# Main.net
KiCad netlist of a schematic drawn in Altium Designer
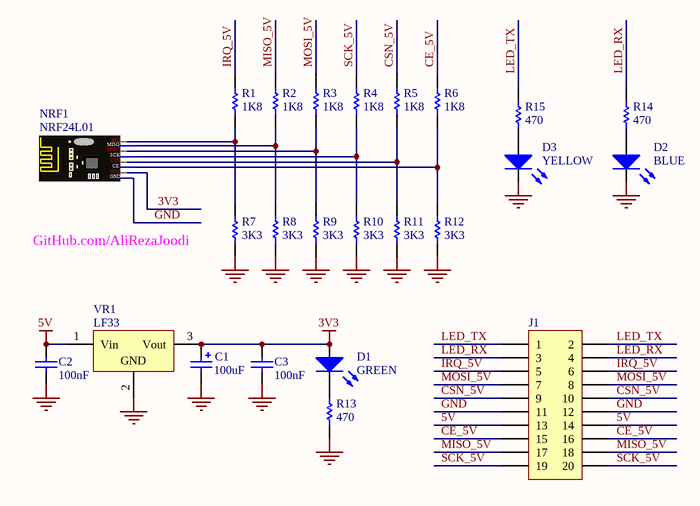
[diagram p0: Main.SchDoc]

(export (version "E")
  (design (tool "Eeschema 10.0.6"))
  (components
    (comp (ref "C1")
      (value "100uF")
      (footprint "CAPPR2.5-6.3x5")
      (description "Polarized Capacitor (Radial)")
      (fields (field (name "MANUFACTURER") "Generic Components") (field (name "PUBLISHER") "Altium Limited"))
      (libsource (lib "Miscellaneous Devices") (part "Cap Pol1"))
    )
    (comp (ref "C2")
      (value "100nF")
      (footprint "CAPNTO2.54-3.05x1.78A")
      (description "Capacitor")
      (fields (field (name "MANUFACTURER") "Generic Components") (field (name "PUBLISHER") "Altium Limited"))
      (libsource (lib "Miscellaneous Devices") (part "Cap"))
    )
    (comp (ref "C3")
      (value "100nF")
      (footprint "CAPNTO2.54-3.05x1.78A")
      (description "Capacitor")
      (fields (field (name "MANUFACTURER") "Generic Components") (field (name "PUBLISHER") "Altium Limited"))
      (libsource (lib "Miscellaneous Devices") (part "Cap"))
    )
    (comp (ref "D1")
      (value "GREEN")
      (footprint "LED-5mm_Red")
      (description "Typical INFRARED GaAs LED")
      (fields (field (name "MANUFACTURER") "Generic Components") (field (name "PUBLISHER") "Altium Limited"))
      (libsource (lib "Miscellaneous Devices") (part "LED"))
    )
    (comp (ref "D2")
      (value "BLUE")
      (footprint "LED-5mm_Red")
      (description "Typical INFRARED GaAs LED")
      (fields (field (name "MANUFACTURER") "Generic Components") (field (name "PUBLISHER") "Altium Limited"))
      (libsource (lib "Miscellaneous Devices") (part "LED"))
    )
    (comp (ref "D3")
      (value "YELLOW")
      (footprint "LED-5mm_Red")
      (description "Typical INFRARED GaAs LED")
      (fields (field (name "MANUFACTURER") "Generic Components") (field (name "PUBLISHER") "Altium Limited"))
      (libsource (lib "Miscellaneous Devices") (part "LED"))
    )
    (comp (ref "J1")
      (value "Header 10X2")
      (footprint "FKV20SN")
      (description "Header, 10-Pin, Dual row")
      (fields (field (name "MANUFACTURER") "Generic Components") (field (name "PUBLISHER") "Altium Limited"))
      (libsource (lib "Miscellaneous Connectors") (part "Header 10X2"))
    )
    (comp (ref "NRF1")
      (value "NRF24L01")
      (footprint "NRF24L01+PA+LNA")
      (libsource (lib "NRF24L01") (part "NRF24L01"))
    )
    (comp (ref "R1")
      (value "1K8")
      (footprint "AXIAL-0.4")
      (description "Resistor")
      (fields (field (name "PUBLISHER") "Altium Limited"))
      (libsource (lib "Miscellaneous Devices") (part "Res1"))
    )
    (comp (ref "R2")
      (value "1K8")
      (footprint "AXIAL-0.4")
      (description "Resistor")
      (fields (field (name "PUBLISHER") "Altium Limited"))
      (libsource (lib "Miscellaneous Devices") (part "Res1"))
    )
    (comp (ref "R3")
      (value "1K8")
      (footprint "AXIAL-0.4")
      (description "Resistor")
      (fields (field (name "PUBLISHER") "Altium Limited"))
      (libsource (lib "Miscellaneous Devices") (part "Res1"))
    )
    (comp (ref "R4")
      (value "1K8")
      (footprint "AXIAL-0.4")
      (description "Resistor")
      (fields (field (name "PUBLISHER") "Altium Limited"))
      (libsource (lib "Miscellaneous Devices") (part "Res1"))
    )
    (comp (ref "R5")
      (value "1K8")
      (footprint "AXIAL-0.4")
      (description "Resistor")
      (fields (field (name "PUBLISHER") "Altium Limited"))
      (libsource (lib "Miscellaneous Devices") (part "Res1"))
    )
    (comp (ref "R6")
      (value "1K8")
      (footprint "AXIAL-0.4")
      (description "Resistor")
      (fields (field (name "PUBLISHER") "Altium Limited"))
      (libsource (lib "Miscellaneous Devices") (part "Res1"))
    )
    (comp (ref "R7")
      (value "3K3")
      (footprint "AXIAL-0.4")
      (description "Resistor")
      (fields (field (name "PUBLISHER") "Altium Limited"))
      (libsource (lib "Miscellaneous Devices") (part "Res1"))
    )
    (comp (ref "R8")
      (value "3K3")
      (footprint "AXIAL-0.4")
      (description "Resistor")
      (fields (field (name "PUBLISHER") "Altium Limited"))
      (libsource (lib "Miscellaneous Devices") (part "Res1"))
    )
    (comp (ref "R9")
      (value "3K3")
      (footprint "AXIAL-0.4")
      (description "Resistor")
      (fields (field (name "PUBLISHER") "Altium Limited"))
      (libsource (lib "Miscellaneous Devices") (part "Res1"))
    )
    (comp (ref "R10")
      (value "3K3")
      (footprint "AXIAL-0.4")
      (description "Resistor")
      (fields (field (name "PUBLISHER") "Altium Limited"))
      (libsource (lib "Miscellaneous Devices") (part "Res1"))
    )
    (comp (ref "R11")
      (value "3K3")
      (footprint "AXIAL-0.4")
      (description "Resistor")
      (fields (field (name "PUBLISHER") "Altium Limited"))
      (libsource (lib "Miscellaneous Devices") (part "Res1"))
    )
    (comp (ref "R12")
      (value "3K3")
      (footprint "AXIAL-0.4")
      (description "Resistor")
      (fields (field (name "PUBLISHER") "Altium Limited"))
      (libsource (lib "Miscellaneous Devices") (part "Res1"))
    )
    (comp (ref "R13")
      (value "470")
      (footprint "AXIAL-0.4")
      (description "Resistor")
      (fields (field (name "PUBLISHER") "Altium Limited"))
      (libsource (lib "Miscellaneous Devices") (part "Res1"))
    )
    (comp (ref "R14")
      (value "470")
      (footprint "AXIAL-0.4")
      (description "Resistor")
      (fields (field (name "PUBLISHER") "Altium Limited"))
      (libsource (lib "Miscellaneous Devices") (part "Res1"))
    )
    (comp (ref "R15")
      (value "470")
      (footprint "AXIAL-0.4")
      (description "Resistor")
      (fields (field (name "PUBLISHER") "Altium Limited"))
      (libsource (lib "Miscellaneous Devices") (part "Res1"))
    )
    (comp (ref "VR1")
      (value "LF33")
      (footprint "TO257H_2")
      (description "Voltage Regulator")
      (fields (field (name "MANUFACTURER") "Generic Components") (field (name "PUBLISHER") "Altium Limited"))
      (libsource (lib "my Libraries") (part "Volt Reg"))
    )
  )
  (nets
    (net (code "1") (name "/CE_5V") (class "Default")
      (node (ref "J1") (pin "15") (pinfunction "15_15") (pintype "passive"))
      (node (ref "J1") (pin "16") (pinfunction "16_16") (pintype "passive"))
      (node (ref "R6") (pin "1") (pinfunction "1_1") (pintype "passive"))
    )
    (net (code "2") (name "/CSN_5V") (class "Default")
      (node (ref "J1") (pin "10") (pinfunction "10_10") (pintype "passive"))
      (node (ref "J1") (pin "9") (pinfunction "9_9") (pintype "passive"))
      (node (ref "R5") (pin "1") (pinfunction "1_1") (pintype "passive"))
    )
    (net (code "3") (name "/IRQ_5V") (class "Default")
      (node (ref "J1") (pin "5") (pinfunction "5_5") (pintype "passive"))
      (node (ref "J1") (pin "6") (pinfunction "6_6") (pintype "passive"))
      (node (ref "R1") (pin "1") (pinfunction "1_1") (pintype "passive"))
    )
    (net (code "4") (name "/LED_RX") (class "Default")
      (node (ref "J1") (pin "3") (pinfunction "3_3") (pintype "passive"))
      (node (ref "J1") (pin "4") (pinfunction "4_4") (pintype "passive"))
      (node (ref "R14") (pin "1") (pinfunction "1_1") (pintype "passive"))
    )
    (net (code "5") (name "/LED_TX") (class "Default")
      (node (ref "J1") (pin "1") (pinfunction "1_1") (pintype "passive"))
      (node (ref "J1") (pin "2") (pinfunction "2_2") (pintype "passive"))
      (node (ref "R15") (pin "1") (pinfunction "1_1") (pintype "passive"))
    )
    (net (code "6") (name "/MISO_5V") (class "Default")
      (node (ref "J1") (pin "17") (pinfunction "17_17") (pintype "passive"))
      (node (ref "J1") (pin "18") (pinfunction "18_18") (pintype "passive"))
      (node (ref "R2") (pin "1") (pinfunction "1_1") (pintype "passive"))
    )
    (net (code "7") (name "/MOSI_5V") (class "Default")
      (node (ref "J1") (pin "7") (pinfunction "7_7") (pintype "passive"))
      (node (ref "J1") (pin "8") (pinfunction "8_8") (pintype "passive"))
      (node (ref "R3") (pin "1") (pinfunction "1_1") (pintype "passive"))
    )
    (net (code "8") (name "/SCK_5V") (class "Default")
      (node (ref "J1") (pin "19") (pinfunction "19_19") (pintype "passive"))
      (node (ref "J1") (pin "20") (pinfunction "20_20") (pintype "passive"))
      (node (ref "R4") (pin "1") (pinfunction "1_1") (pintype "passive"))
    )
    (net (code "9") (name "3V3") (class "Default")
      (node (ref "C1") (pin "1") (pinfunction "1_1") (pintype "passive"))
      (node (ref "C3") (pin "2") (pinfunction "2_2") (pintype "passive"))
      (node (ref "D1") (pin "1") (pinfunction "A_1") (pintype "passive"))
      (node (ref "NRF1") (pin "VCC") (pinfunction "VCC_VCC") (pintype "power_in"))
      (node (ref "VR1") (pin "3") (pinfunction "Vout_3") (pintype "passive"))
    )
    (net (code "10") (name "5V") (class "Default")
      (node (ref "C2") (pin "2") (pinfunction "2_2") (pintype "passive"))
      (node (ref "J1") (pin "13") (pinfunction "13_13") (pintype "passive"))
      (node (ref "J1") (pin "14") (pinfunction "14_14") (pintype "passive"))
      (node (ref "VR1") (pin "1") (pinfunction "Vin_1") (pintype "passive"))
    )
    (net (code "11") (name "GND") (class "Default")
      (node (ref "C1") (pin "2") (pinfunction "2_2") (pintype "passive"))
      (node (ref "C2") (pin "1") (pinfunction "1_1") (pintype "passive"))
      (node (ref "C3") (pin "1") (pinfunction "1_1") (pintype "passive"))
      (node (ref "D2") (pin "2") (pinfunction "K_2") (pintype "passive"))
      (node (ref "D3") (pin "2") (pinfunction "K_2") (pintype "passive"))
      (node (ref "J1") (pin "11") (pinfunction "11_11") (pintype "passive"))
      (node (ref "J1") (pin "12") (pinfunction "12_12") (pintype "passive"))
      (node (ref "NRF1") (pin "GND") (pinfunction "GND_GND") (pintype "power_in"))
      (node (ref "R10") (pin "2") (pinfunction "2_2") (pintype "passive"))
      (node (ref "R11") (pin "2") (pinfunction "2_2") (pintype "passive"))
      (node (ref "R12") (pin "2") (pinfunction "2_2") (pintype "passive"))
      (node (ref "R13") (pin "2") (pinfunction "2_2") (pintype "passive"))
      (node (ref "R7") (pin "2") (pinfunction "2_2") (pintype "passive"))
      (node (ref "R8") (pin "2") (pinfunction "2_2") (pintype "passive"))
      (node (ref "R9") (pin "2") (pinfunction "2_2") (pintype "passive"))
      (node (ref "VR1") (pin "2") (pinfunction "GND_2") (pintype "passive"))
    )
    (net (code "12") (name "Net-(D1-K)") (class "Default")
      (node (ref "D1") (pin "2") (pinfunction "K_2") (pintype "passive"))
      (node (ref "R13") (pin "1") (pinfunction "1_1") (pintype "passive"))
    )
    (net (code "13") (name "Net-(D2-A)") (class "Default")
      (node (ref "D2") (pin "1") (pinfunction "A_1") (pintype "passive"))
      (node (ref "R14") (pin "2") (pinfunction "2_2") (pintype "passive"))
    )
    (net (code "14") (name "Net-(D3-A)") (class "Default")
      (node (ref "D3") (pin "1") (pinfunction "A_1") (pintype "passive"))
      (node (ref "R15") (pin "2") (pinfunction "2_2") (pintype "passive"))
    )
    (net (code "15") (name "Net-(NRF1-PadCE)") (class "Default")
      (node (ref "NRF1") (pin "CE") (pinfunction "CE_CE") (pintype "passive"))
      (node (ref "R12") (pin "1") (pinfunction "1_1") (pintype "passive"))
      (node (ref "R6") (pin "2") (pinfunction "2_2") (pintype "passive"))
    )
    (net (code "16") (name "Net-(NRF1-PadCSN)") (class "Default")
      (node (ref "NRF1") (pin "CSN") (pinfunction "CSN_CSN") (pintype "passive"))
      (node (ref "R11") (pin "1") (pinfunction "1_1") (pintype "passive"))
      (node (ref "R5") (pin "2") (pinfunction "2_2") (pintype "passive"))
    )
    (net (code "17") (name "Net-(NRF1-PadIRQ)") (class "Default")
      (node (ref "NRF1") (pin "IRQ") (pinfunction "IRQ_IRQ") (pintype "passive"))
      (node (ref "R1") (pin "2") (pinfunction "2_2") (pintype "passive"))
      (node (ref "R7") (pin "1") (pinfunction "1_1") (pintype "passive"))
    )
    (net (code "18") (name "Net-(NRF1-PadMISO)") (class "Default")
      (node (ref "NRF1") (pin "MISO") (pinfunction "MISO_MISO") (pintype "passive"))
      (node (ref "R2") (pin "2") (pinfunction "2_2") (pintype "passive"))
      (node (ref "R8") (pin "1") (pinfunction "1_1") (pintype "passive"))
    )
    (net (code "19") (name "Net-(NRF1-PadMOSI)") (class "Default")
      (node (ref "NRF1") (pin "MOSI") (pinfunction "MOSI_MOSI") (pintype "passive"))
      (node (ref "R3") (pin "2") (pinfunction "2_2") (pintype "passive"))
      (node (ref "R9") (pin "1") (pinfunction "1_1") (pintype "passive"))
    )
    (net (code "20") (name "Net-(NRF1-PadSCK)") (class "Default")
      (node (ref "NRF1") (pin "SCK") (pinfunction "SCK_SCK") (pintype "passive"))
      (node (ref "R10") (pin "1") (pinfunction "1_1") (pintype "passive"))
      (node (ref "R4") (pin "2") (pinfunction "2_2") (pintype "passive"))
    )
  )
)
